# usb_usb2534.net
KiCad netlist of a schematic drawn in Altium Designer
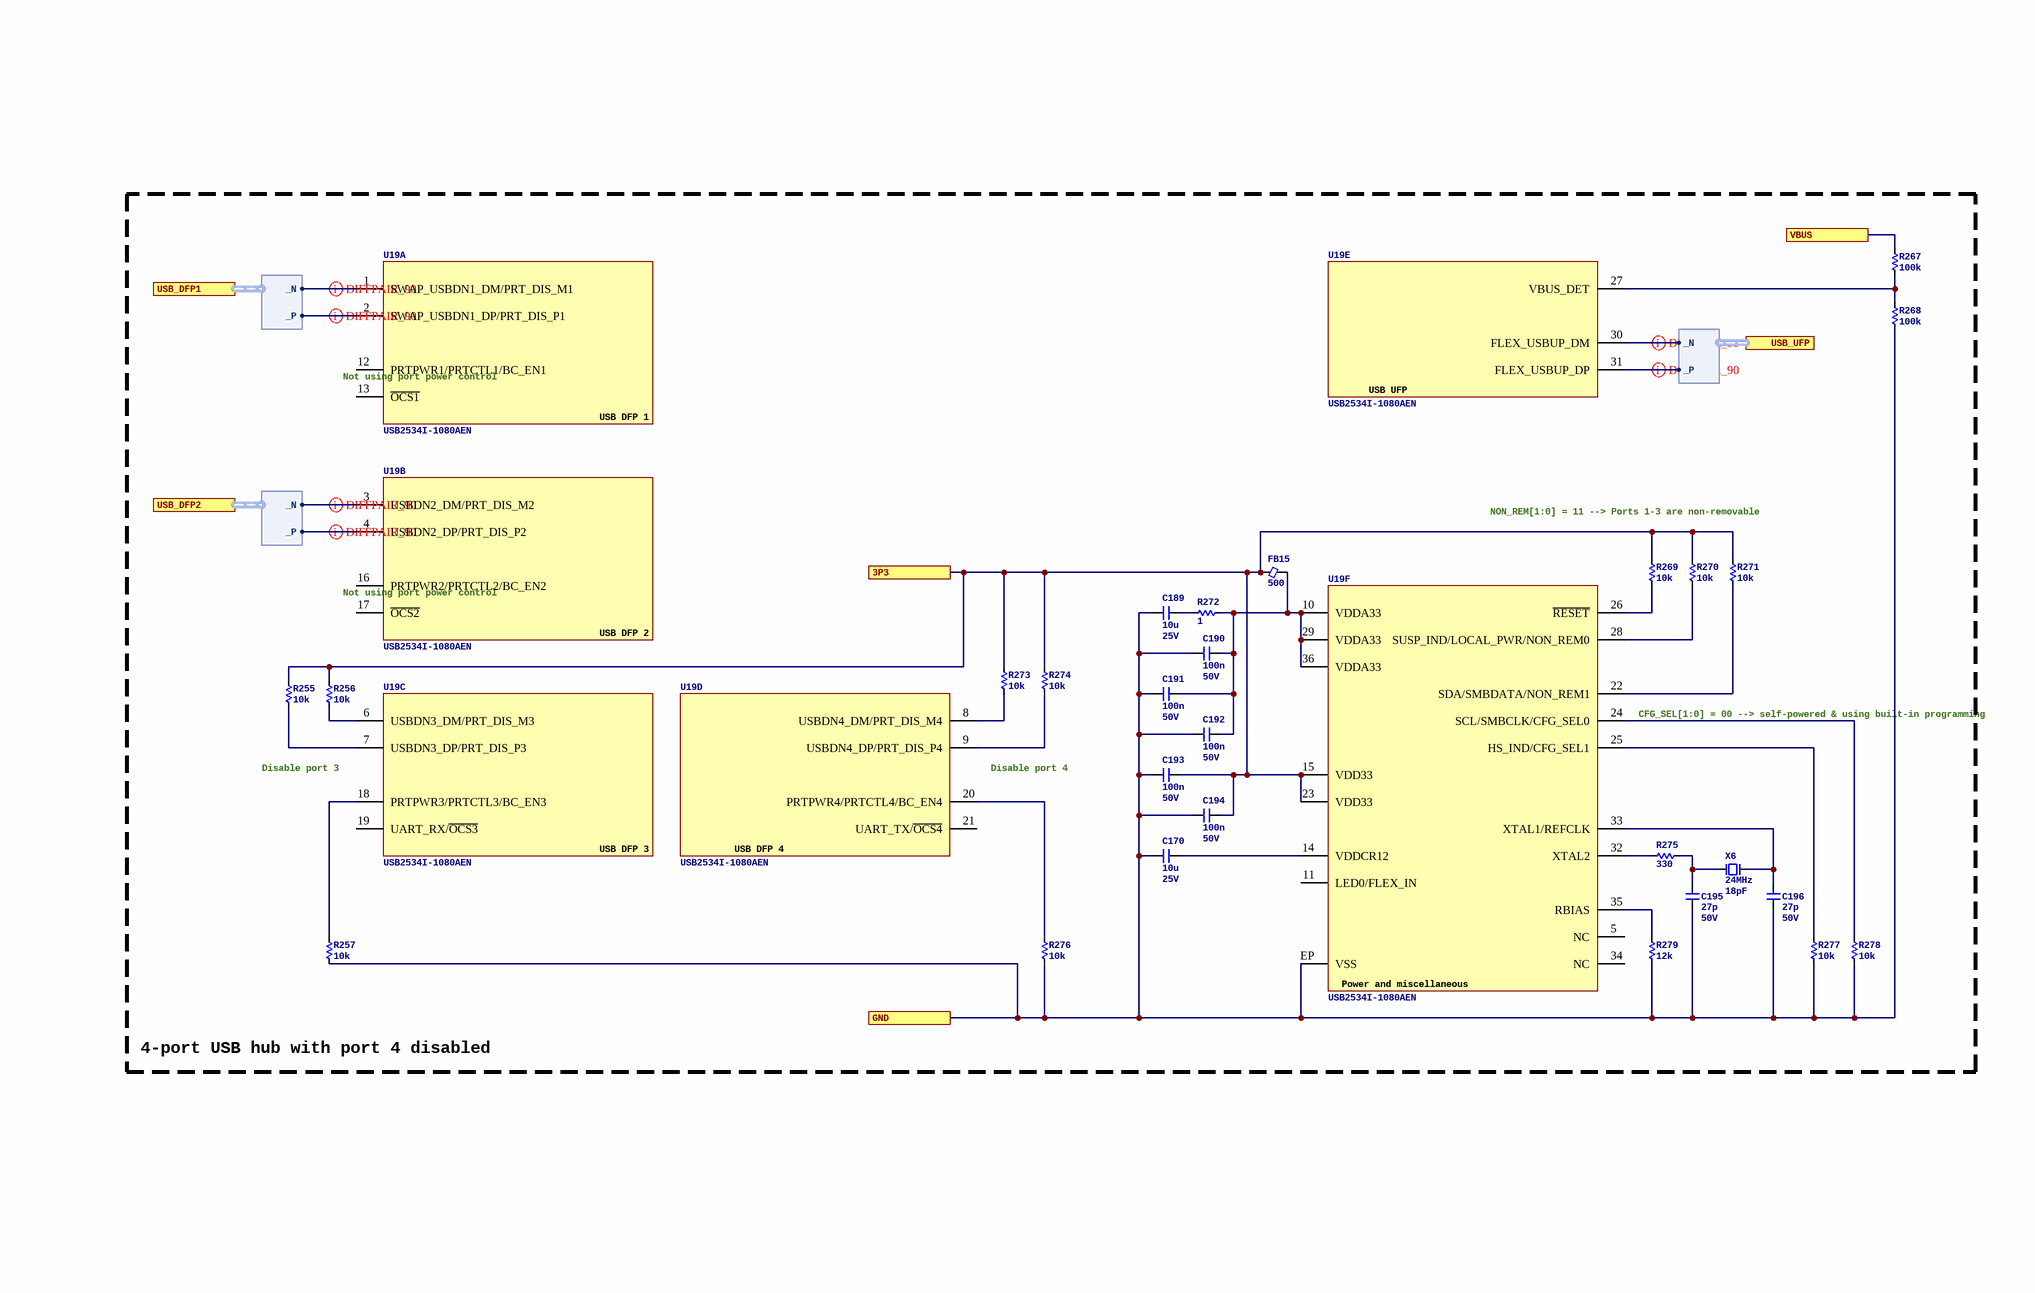
[diagram p0: usb_usb2534.SchDoc]

(export (version "E")
  (design (tool "Eeschema 10.0.6"))
  (components
    (comp (ref "C170")
      (value "CL10A106MA8NRNC")
      (footprint "C0603")
      (fields
        (field (name "CAPACITANCE") "10u")
        (field (name "MANUFACTURER") "Samsung Electro-Mechanics")
        (field (name "VOLTAGE RATING") "25V")
      )
      (libsource (lib "database") (part "__template_cap"))
    )
    (comp (ref "C189")
      (value "CL21B106KAYQNNE")
      (footprint "C0805")
      (fields
        (field (name "CAPACITANCE") "10u")
        (field (name "MANUFACTURER") "Samsung Electro-Mechanics")
        (field (name "VOLTAGE RATING") "25V")
      )
      (libsource (lib "database") (part "__template_cap"))
    )
    (comp (ref "C190")
      (value "CL05B104KB54PNC")
      (footprint "C0402")
      (fields
        (field (name "CAPACITANCE") "100n")
        (field (name "MANUFACTURER") "Samsung Electro-Mechanics")
        (field (name "VOLTAGE RATING") "50V")
      )
      (libsource (lib "database") (part "__template_cap"))
    )
    (comp (ref "C191")
      (value "CL05B104KB54PNC")
      (footprint "C0402")
      (fields
        (field (name "CAPACITANCE") "100n")
        (field (name "MANUFACTURER") "Samsung Electro-Mechanics")
        (field (name "VOLTAGE RATING") "50V")
      )
      (libsource (lib "database") (part "__template_cap"))
    )
    (comp (ref "C192")
      (value "CL05B104KB54PNC")
      (footprint "C0402")
      (fields
        (field (name "CAPACITANCE") "100n")
        (field (name "MANUFACTURER") "Samsung Electro-Mechanics")
        (field (name "VOLTAGE RATING") "50V")
      )
      (libsource (lib "database") (part "__template_cap"))
    )
    (comp (ref "C193")
      (value "CL05B104KB54PNC")
      (footprint "C0402")
      (fields
        (field (name "CAPACITANCE") "100n")
        (field (name "MANUFACTURER") "Samsung Electro-Mechanics")
        (field (name "VOLTAGE RATING") "50V")
      )
      (libsource (lib "database") (part "__template_cap"))
    )
    (comp (ref "C194")
      (value "CL05B104KB54PNC")
      (footprint "C0402")
      (fields
        (field (name "CAPACITANCE") "100n")
        (field (name "MANUFACTURER") "Samsung Electro-Mechanics")
        (field (name "VOLTAGE RATING") "50V")
      )
      (libsource (lib "database") (part "__template_cap"))
    )
    (comp (ref "C195")
      (value "0402CG270J500NT")
      (footprint "C0402")
      (fields
        (field (name "CAPACITANCE") "27p")
        (field (name "MANUFACTURER") "FH(Guangdong Fenghua Advanced Tech)")
        (field (name "VOLTAGE RATING") "50V")
      )
      (libsource (lib "database") (part "__template_cap"))
    )
    (comp (ref "C196")
      (value "0402CG270J500NT")
      (footprint "C0402")
      (fields
        (field (name "CAPACITANCE") "27p")
        (field (name "MANUFACTURER") "FH(Guangdong Fenghua Advanced Tech)")
        (field (name "VOLTAGE RATING") "50V")
      )
      (libsource (lib "database") (part "__template_cap"))
    )
    (comp (ref "FB15")
      (value "BLM15AX601SN1D")
      (footprint "FB0402")
      (fields (field (name "MANUFACTURER") "Murata Electronics") (field (name "CURRENT RATING (MA)") "500"))
      (libsource (lib "database") (part "__template_fb"))
    )
    (comp (ref "R255")
      (value "10k")
      (footprint "R0402")
      (fields
        (field (name "TOLERANCE") "1%")
        (field (name "MANUFACTURER PART NUMBER") "0402WGF1002TCE")
        (field (name "MANUFACTURER") "UNI-ROYAL(Uniroyal Elec)")
      )
      (libsource (lib "database") (part "__template_resistor"))
    )
    (comp (ref "R256")
      (value "10k")
      (footprint "R0402")
      (fields
        (field (name "TOLERANCE") "1%")
        (field (name "MANUFACTURER PART NUMBER") "0402WGF1002TCE")
        (field (name "MANUFACTURER") "UNI-ROYAL(Uniroyal Elec)")
      )
      (libsource (lib "database") (part "__template_resistor"))
    )
    (comp (ref "R257")
      (value "10k")
      (footprint "R0402")
      (fields
        (field (name "TOLERANCE") "1%")
        (field (name "MANUFACTURER PART NUMBER") "0402WGF1002TCE")
        (field (name "MANUFACTURER") "UNI-ROYAL(Uniroyal Elec)")
      )
      (libsource (lib "database") (part "__template_resistor"))
    )
    (comp (ref "R267")
      (value "100k")
      (footprint "R0402")
      (fields
        (field (name "TOLERANCE") "1%")
        (field (name "MANUFACTURER PART NUMBER") "0402WGF1003TCE")
        (field (name "MANUFACTURER") "UNI-ROYAL(Uniroyal Elec)")
      )
      (libsource (lib "database") (part "__template_resistor"))
    )
    (comp (ref "R268")
      (value "100k")
      (footprint "R0402")
      (fields
        (field (name "TOLERANCE") "1%")
        (field (name "MANUFACTURER PART NUMBER") "0402WGF1003TCE")
        (field (name "MANUFACTURER") "UNI-ROYAL(Uniroyal Elec)")
      )
      (libsource (lib "database") (part "__template_resistor"))
    )
    (comp (ref "R269")
      (value "10k")
      (footprint "R0402")
      (fields
        (field (name "TOLERANCE") "1%")
        (field (name "MANUFACTURER PART NUMBER") "0402WGF1002TCE")
        (field (name "MANUFACTURER") "UNI-ROYAL(Uniroyal Elec)")
      )
      (libsource (lib "database") (part "__template_resistor"))
    )
    (comp (ref "R270")
      (value "10k")
      (footprint "R0402")
      (fields
        (field (name "TOLERANCE") "1%")
        (field (name "MANUFACTURER PART NUMBER") "0402WGF1002TCE")
        (field (name "MANUFACTURER") "UNI-ROYAL(Uniroyal Elec)")
      )
      (libsource (lib "database") (part "__template_resistor"))
    )
    (comp (ref "R271")
      (value "10k")
      (footprint "R0402")
      (fields
        (field (name "TOLERANCE") "1%")
        (field (name "MANUFACTURER PART NUMBER") "0402WGF1002TCE")
        (field (name "MANUFACTURER") "UNI-ROYAL(Uniroyal Elec)")
      )
      (libsource (lib "database") (part "__template_resistor"))
    )
    (comp (ref "R272")
      (value "1")
      (footprint "R0402")
      (fields
        (field (name "TOLERANCE") "1%")
        (field (name "MANUFACTURER PART NUMBER") "CRCW04021R00FKED")
        (field (name "MANUFACTURER") "Vishay Intertech")
      )
      (libsource (lib "database") (part "__template_resistor"))
    )
    (comp (ref "R273")
      (value "10k")
      (footprint "R0402")
      (fields
        (field (name "TOLERANCE") "1%")
        (field (name "MANUFACTURER PART NUMBER") "0402WGF1002TCE")
        (field (name "MANUFACTURER") "UNI-ROYAL(Uniroyal Elec)")
      )
      (libsource (lib "database") (part "__template_resistor"))
    )
    (comp (ref "R274")
      (value "10k")
      (footprint "R0402")
      (fields
        (field (name "TOLERANCE") "1%")
        (field (name "MANUFACTURER PART NUMBER") "0402WGF1002TCE")
        (field (name "MANUFACTURER") "UNI-ROYAL(Uniroyal Elec)")
      )
      (libsource (lib "database") (part "__template_resistor"))
    )
    (comp (ref "R275")
      (value "330")
      (footprint "R0402")
      (fields
        (field (name "TOLERANCE") "1%")
        (field (name "MANUFACTURER PART NUMBER") "0402WGF3300TCE")
        (field (name "MANUFACTURER") "UNI-ROYAL(Uniroyal Elec)")
      )
      (libsource (lib "database") (part "__template_resistor"))
    )
    (comp (ref "R276")
      (value "10k")
      (footprint "R0402")
      (fields
        (field (name "TOLERANCE") "1%")
        (field (name "MANUFACTURER PART NUMBER") "0402WGF1002TCE")
        (field (name "MANUFACTURER") "UNI-ROYAL(Uniroyal Elec)")
      )
      (libsource (lib "database") (part "__template_resistor"))
    )
    (comp (ref "R277")
      (value "10k")
      (footprint "R0402")
      (fields
        (field (name "TOLERANCE") "1%")
        (field (name "MANUFACTURER PART NUMBER") "0402WGF1002TCE")
        (field (name "MANUFACTURER") "UNI-ROYAL(Uniroyal Elec)")
      )
      (libsource (lib "database") (part "__template_resistor"))
    )
    (comp (ref "R278")
      (value "10k")
      (footprint "R0402")
      (fields
        (field (name "TOLERANCE") "1%")
        (field (name "MANUFACTURER PART NUMBER") "0402WGF1002TCE")
        (field (name "MANUFACTURER") "UNI-ROYAL(Uniroyal Elec)")
      )
      (libsource (lib "database") (part "__template_resistor"))
    )
    (comp (ref "R279")
      (value "12k")
      (footprint "R0402")
      (fields
        (field (name "TOLERANCE") "1%")
        (field (name "MANUFACTURER PART NUMBER") "0402WGF1202TCE")
        (field (name "MANUFACTURER") "UNI-ROYAL(Uniroyal Elec)")
      )
      (libsource (lib "database") (part "__template_resistor"))
    )
    (comp (ref "U19")
      (value "USB2534I-1080AEN")
      (footprint "QFN50P600X600X90-36N")
      (description "USB Bus Controller, CMOS")
      (fields (field (name "MANUFACTURER") "Microchip"))
      (libsource (lib "SSCP") (part "USB_HUB_4PORT_USB2534I-1080AEN"))
    )
    (comp (ref "X6")
      (value "7A-24.000MAAJ-T")
      (footprint "XTAL_TXC_7A")
      (description "CRYSTAL 24.000 MHZ 18PF SMD")
      (fields
        (field (name "FREQUENCY") "24MHz")
        (field (name "LOAD CAPACITANCE") "18pF")
        (field (name "MANUFACTURER") "TXC CORPORATION")
      )
      (libsource (lib "SSCP") (part "XTAL_7A-24.000MAAJ-T"))
    )
  )
  (nets
    (net (code "2") (name "/3P3") (class "Default")
      (node (ref "C193") (pin "1") (pintype "passive"))
      (node (ref "C194") (pin "1") (pintype "passive"))
      (node (ref "FB15") (pin "1") (pintype "passive"))
      (node (ref "R255") (pin "1") (pintype "passive"))
      (node (ref "R256") (pin "1") (pintype "passive"))
      (node (ref "R269") (pin "1") (pintype "passive"))
      (node (ref "R270") (pin "1") (pintype "passive"))
      (node (ref "R271") (pin "1") (pintype "passive"))
      (node (ref "R273") (pin "1") (pintype "passive"))
      (node (ref "R274") (pin "1") (pintype "passive"))
      (node (ref "U19") (pin "15") (pinfunction "VDD33_15") (pintype "passive"))
      (node (ref "U19") (pin "23") (pinfunction "VDD33_23") (pintype "passive"))
    )
    (net (code "3") (name "/GND") (class "Default")
      (node (ref "C170") (pin "2") (pintype "passive"))
      (node (ref "C189") (pin "2") (pintype "passive"))
      (node (ref "C190") (pin "2") (pintype "passive"))
      (node (ref "C191") (pin "2") (pintype "passive"))
      (node (ref "C192") (pin "2") (pintype "passive"))
      (node (ref "C193") (pin "2") (pintype "passive"))
      (node (ref "C194") (pin "2") (pintype "passive"))
      (node (ref "C195") (pin "2") (pintype "passive"))
      (node (ref "C196") (pin "2") (pintype "passive"))
      (node (ref "R257") (pin "2") (pintype "passive"))
      (node (ref "R268") (pin "1") (pintype "passive"))
      (node (ref "R276") (pin "2") (pintype "passive"))
      (node (ref "R277") (pin "2") (pintype "passive"))
      (node (ref "R278") (pin "2") (pintype "passive"))
      (node (ref "R279") (pin "2") (pintype "passive"))
      (node (ref "U19") (pin "EP") (pinfunction "VSS_EP") (pintype "passive"))
    )
    (net (code "4") (name "/VBUS") (class "Default") (node (ref "R267") (pin "1") (pintype "passive")))
    (net (code "6") (name "Net-(C189-Pad1)") (class "Default")
      (node (ref "C189") (pin "1") (pintype "passive"))
      (node (ref "R272") (pin "2") (pintype "passive"))
    )
    (net (code "7") (name "Net-(C190-Pad1)") (class "Default")
      (node (ref "C190") (pin "1") (pintype "passive"))
      (node (ref "C191") (pin "1") (pintype "passive"))
      (node (ref "C192") (pin "1") (pintype "passive"))
      (node (ref "FB15") (pin "2") (pintype "passive"))
      (node (ref "R272") (pin "1") (pintype "passive"))
      (node (ref "U19") (pin "10") (pinfunction "VDDA33_10") (pintype "passive"))
      (node (ref "U19") (pin "29") (pinfunction "VDDA33_29") (pintype "passive"))
      (node (ref "U19") (pin "36") (pinfunction "VDDA33_36") (pintype "passive"))
    )
    (net (code "8") (name "Net-(C195-Pad1)") (class "Default")
      (node (ref "C195") (pin "1") (pintype "passive"))
      (node (ref "R275") (pin "1") (pintype "passive"))
      (node (ref "X6") (pin "1") (pinfunction "1_1") (pintype "passive"))
    )
    (net (code "9") (name "Net-(U19C-PRTPWR3{slash}PRTCTL3{slash}BC_EN3)") (class "Default")
      (node (ref "R257") (pin "1") (pintype "passive"))
      (node (ref "U19") (pin "18") (pinfunction "PRTPWR3/PRTCTL3/BC_EN3_18") (pintype "passive"))
    )
    (net (code "10") (name "Net-(U19C-USBDN3_DM{slash}PRT_DIS_M3)") (class "Default")
      (node (ref "R256") (pin "2") (pintype "passive"))
      (node (ref "U19") (pin "6") (pinfunction "USBDN3_DM/PRT_DIS_M3_6") (pintype "passive"))
    )
    (net (code "11") (name "Net-(U19C-USBDN3_DP{slash}PRT_DIS_P3)") (class "Default")
      (node (ref "R255") (pin "2") (pintype "passive"))
      (node (ref "U19") (pin "7") (pinfunction "USBDN3_DP/PRT_DIS_P3_7") (pintype "passive"))
    )
    (net (code "12") (name "Net-(U19D-PRTPWR4{slash}PRTCTL4{slash}BC_EN4)") (class "Default")
      (node (ref "R276") (pin "1") (pintype "passive"))
      (node (ref "U19") (pin "20") (pinfunction "PRTPWR4/PRTCTL4/BC_EN4_20") (pintype "passive"))
    )
    (net (code "13") (name "Net-(U19D-USBDN4_DM{slash}PRT_DIS_M4)") (class "Default")
      (node (ref "R273") (pin "2") (pintype "passive"))
      (node (ref "U19") (pin "8") (pinfunction "USBDN4_DM/PRT_DIS_M4_8") (pintype "passive"))
    )
    (net (code "14") (name "Net-(U19D-USBDN4_DP{slash}PRT_DIS_P4)") (class "Default")
      (node (ref "R274") (pin "2") (pintype "passive"))
      (node (ref "U19") (pin "9") (pinfunction "USBDN4_DP/PRT_DIS_P4_9") (pintype "passive"))
    )
    (net (code "15") (name "Net-(U19E-VBUS_DET)") (class "Default")
      (node (ref "R267") (pin "2") (pintype "passive"))
      (node (ref "R268") (pin "2") (pintype "passive"))
      (node (ref "U19") (pin "27") (pinfunction "VBUS_DET_27") (pintype "passive"))
    )
    (net (code "16") (name "Net-(U19F-HS_IND{slash}CFG_SEL1)") (class "Default")
      (node (ref "R277") (pin "1") (pintype "passive"))
      (node (ref "U19") (pin "25") (pinfunction "HS_IND/CFG_SEL1_25") (pintype "passive"))
    )
    (net (code "17") (name "Net-(U19F-RBIAS)") (class "Default")
      (node (ref "R279") (pin "1") (pintype "passive"))
      (node (ref "U19") (pin "35") (pinfunction "RBIAS_35") (pintype "passive"))
    )
    (net (code "18") (name "Net-(U19F-SCL{slash}SMBCLK{slash}CFG_SEL0)") (class "Default")
      (node (ref "R278") (pin "1") (pintype "passive"))
      (node (ref "U19") (pin "24") (pinfunction "SCL/SMBCLK/CFG_SEL0_24") (pintype "passive"))
    )
    (net (code "19") (name "Net-(U19F-SDA{slash}SMBDATA{slash}NON_REM1)") (class "Default")
      (node (ref "R271") (pin "2") (pintype "passive"))
      (node (ref "U19") (pin "22") (pinfunction "SDA/SMBDATA/NON_REM1_22") (pintype "passive"))
    )
    (net (code "20") (name "Net-(U19F-SUSP_IND{slash}LOCAL_PWR{slash}NON_REM0)") (class "Default")
      (node (ref "R270") (pin "2") (pintype "passive"))
      (node (ref "U19") (pin "28") (pinfunction "SUSP_IND/LOCAL_PWR/NON_REM0_28") (pintype "passive"))
    )
    (net (code "21") (name "Net-(U19F-VDDCR12)") (class "Default")
      (node (ref "C170") (pin "1") (pintype "passive"))
      (node (ref "U19") (pin "14") (pinfunction "VDDCR12_14") (pintype "passive"))
    )
    (net (code "22") (name "Net-(U19F-XTAL1{slash}REFCLK)") (class "Default")
      (node (ref "C196") (pin "1") (pintype "passive"))
      (node (ref "U19") (pin "33") (pinfunction "XTAL1/REFCLK_33") (pintype "passive"))
      (node (ref "X6") (pin "2") (pinfunction "2_2") (pintype "passive"))
    )
    (net (code "23") (name "Net-(U19F-XTAL2)") (class "Default")
      (node (ref "R275") (pin "2") (pintype "passive"))
      (node (ref "U19") (pin "32") (pinfunction "XTAL2_32") (pintype "passive"))
    )
    (net (code "24") (name "Net-(U19F-~{RESET})") (class "Default")
      (node (ref "R269") (pin "2") (pintype "passive"))
      (node (ref "U19") (pin "26") (pinfunction "~{RESET}_26") (pintype "passive"))
    )
    (net (code "25") (name "unconnected-(U19A-PRTPWR1{slash}PRTCTL1{slash}BC_EN1-Pad12)") (class "Default")
      (node (ref "U19") (pin "12") (pinfunction "PRTPWR1/PRTCTL1/BC_EN1_12") (pintype "passive"))
    )
    (net (code "26") (name "unconnected-(U19A-SWAP_USBDN1_DM{slash}PRT_DIS_M1-Pad1)") (class "Default")
      (node (ref "U19") (pin "1") (pinfunction "SWAP_USBDN1_DM/PRT_DIS_M1_1") (pintype "passive"))
    )
    (net (code "27") (name "unconnected-(U19A-SWAP_USBDN1_DP{slash}PRT_DIS_P1-Pad2)") (class "Default")
      (node (ref "U19") (pin "2") (pinfunction "SWAP_USBDN1_DP/PRT_DIS_P1_2") (pintype "passive"))
    )
    (net (code "28") (name "unconnected-(U19A-~{OCS1}-Pad13)") (class "Default")
      (node (ref "U19") (pin "13") (pinfunction "~{OCS1}_13") (pintype "passive"))
    )
    (net (code "29") (name "unconnected-(U19B-PRTPWR2{slash}PRTCTL2{slash}BC_EN2-Pad16)") (class "Default")
      (node (ref "U19") (pin "16") (pinfunction "PRTPWR2/PRTCTL2/BC_EN2_16") (pintype "passive"))
    )
    (net (code "30") (name "unconnected-(U19B-USBDN2_DM{slash}PRT_DIS_M2-Pad3)") (class "Default")
      (node (ref "U19") (pin "3") (pinfunction "USBDN2_DM/PRT_DIS_M2_3") (pintype "passive"))
    )
    (net (code "31") (name "unconnected-(U19B-USBDN2_DP{slash}PRT_DIS_P2-Pad4)") (class "Default")
      (node (ref "U19") (pin "4") (pinfunction "USBDN2_DP/PRT_DIS_P2_4") (pintype "passive"))
    )
    (net (code "32") (name "unconnected-(U19B-~{OCS2}-Pad17)") (class "Default")
      (node (ref "U19") (pin "17") (pinfunction "~{OCS2}_17") (pintype "passive"))
    )
    (net (code "33") (name "unconnected-(U19C-UART_RX{slash}~{OCS3}-Pad19)") (class "Default")
      (node (ref "U19") (pin "19") (pinfunction "UART_RX/~{OCS3}_19") (pintype "passive"))
    )
    (net (code "34") (name "unconnected-(U19D-UART_TX{slash}~{OCS4}-Pad21)") (class "Default")
      (node (ref "U19") (pin "21") (pinfunction "UART_TX/~{OCS4}_21") (pintype "passive"))
    )
    (net (code "35") (name "unconnected-(U19E-FLEX_USBUP_DM-Pad30)") (class "Default")
      (node (ref "U19") (pin "30") (pinfunction "FLEX_USBUP_DM_30") (pintype "passive"))
    )
    (net (code "36") (name "unconnected-(U19E-FLEX_USBUP_DP-Pad31)") (class "Default")
      (node (ref "U19") (pin "31") (pinfunction "FLEX_USBUP_DP_31") (pintype "passive"))
    )
    (net (code "37") (name "unconnected-(U19F-LED0{slash}FLEX_IN-Pad11)") (class "Default")
      (node (ref "U19") (pin "11") (pinfunction "LED0/FLEX_IN_11") (pintype "passive"))
    )
    (net (code "38") (name "unconnected-(U19F-NC-Pad5)") (class "Default")
      (node (ref "U19") (pin "5") (pinfunction "NC_5") (pintype "passive"))
    )
    (net (code "39") (name "unconnected-(U19F-NC-Pad34)") (class "Default")
      (node (ref "U19") (pin "34") (pinfunction "NC_34") (pintype "passive"))
    )
  )
)
